# Hike_Buddy_Schematic.net
KiCad netlist of a schematic drawn in Altium Designer
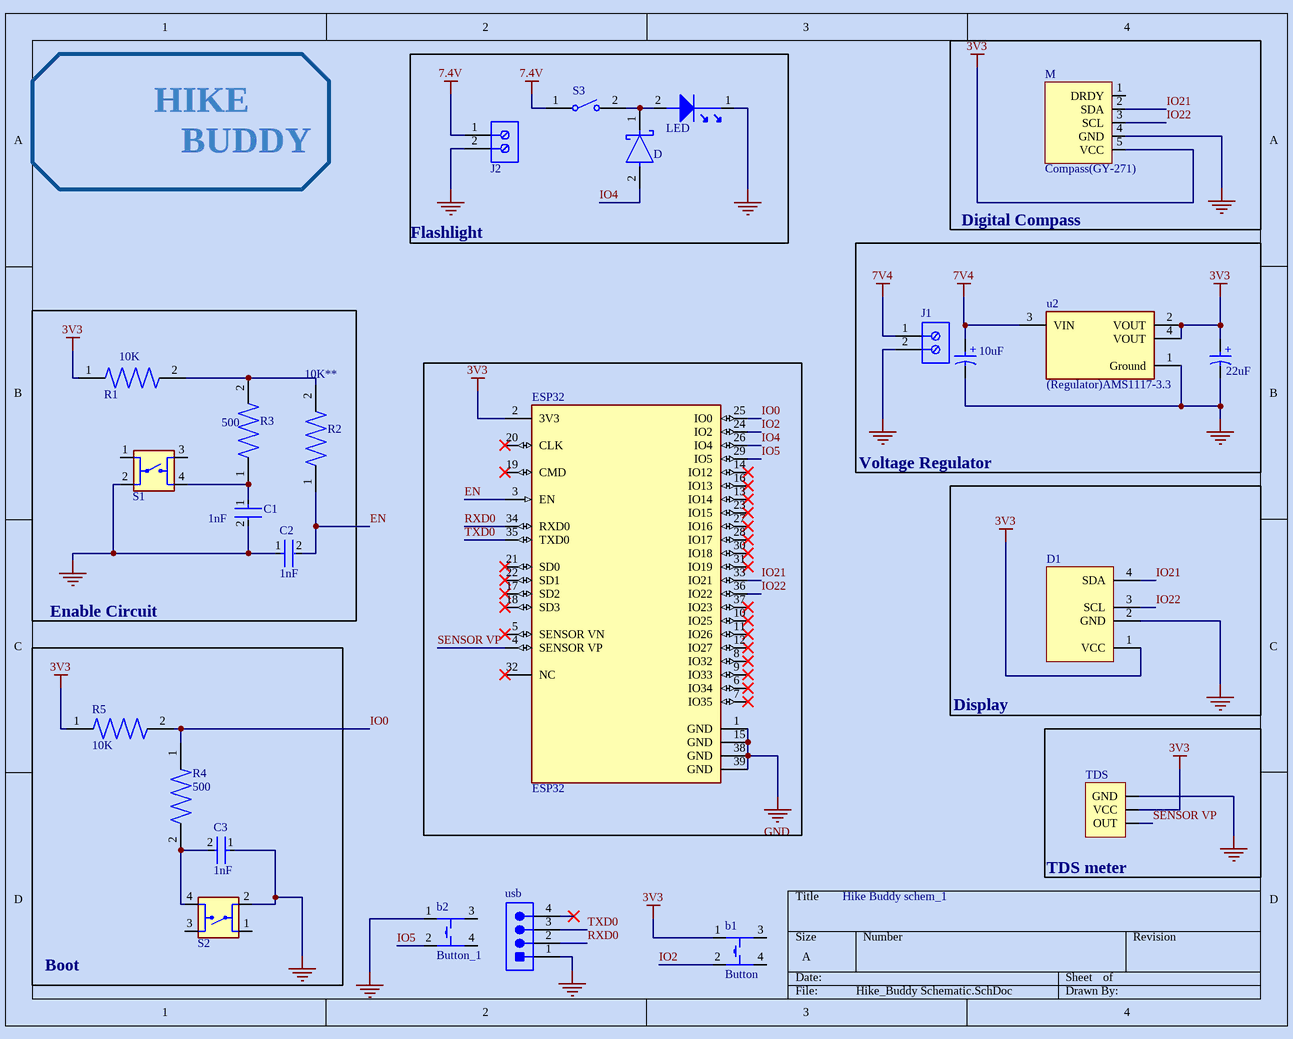
[diagram p0: Hike_Buddy Schematic.SchDoc]

(export (version "E")
  (design (tool "Eeschema 10.0.6"))
  (components
    (comp (ref "10uF")
      (value "860010372001")
      (footprint "WCAP-ATG8_D5H11")
      (description "860010372001 Cap Aluminum Lytic 10uF 16V 20% (5 X 11mm) Radial 2mm 44mA 2000h 85C")
      (fields (field (name "TOLERANCE") "20%"))
      (libsource (lib "Altium Content Vault") (part "Capacitor_Polarized"))
    )
    (comp (ref "22uF")
      (value "860020472004")
      (footprint "WCAP-ATG5_D5H11")
      (description "860020472004 WCAP-ATG5 Aluminum Electrolytic Capacitors")
      (fields (field (name "TOLERANCE") "20%"))
      (libsource (lib "Altium Content Vault") (part "Capacitor_Polarized"))
    )
    (comp (ref "b1")
      (value "Button")
      (footprint "Push Button")
      (libsource (lib "Hike_Buddy") (part "Button"))
    )
    (comp (ref "b2")
      (value "Button_1")
      (footprint "Push Button")
      (libsource (lib "Hike_Buddy") (part "Button_1"))
    )
    (comp (ref "C1")
      (value "1nF")
      (footprint "FP-VY2102M29Y5US6TV7-MFG")
      (fields (field (name "VOLTAGE") "300V") (field (name "TOLERANCE") "20%"))
      (libsource (lib "Altium Content Vault") (part "11868f565c42a9108669ba33697ecf6"))
    )
    (comp (ref "C2")
      (value "1nF")
      (footprint "FP-VY2102M29Y5US6TV7-MFG")
      (fields (field (name "VOLTAGE") "300V") (field (name "TOLERANCE") "20%"))
      (libsource (lib "Altium Content Vault") (part "11868f565c42a9108669ba33697ecf6"))
    )
    (comp (ref "C3")
      (value "1nF")
      (footprint "FP-VY2102M29Y5US6TV7-MFG")
      (fields (field (name "VOLTAGE") "300V") (field (name "TOLERANCE") "20%"))
      (libsource (lib "Altium Content Vault") (part "11868f565c42a9108669ba33697ecf6"))
    )
    (comp (ref "D")
      (value "1N5817")
      (footprint "FP-DO-41-MFG")
      (description "DIODE SCHOTTKY 20V 1A DO41")
      (libsource (lib "Altium Content Vault") (part "1d6ec82d83fb6aee721767c19dac4b9"))
    )
    (comp (ref "D1")
      (value "OLED Display")
      (footprint "Display")
      (description "0.96 inch 128X64 OLED Display Module Blue I2C IIC")
      (libsource (lib "Hike_Buddy") (part "Display"))
    )
    (comp (ref "ESP32")
      (value "ESP32")
      (footprint "ESP32")
      (description "ESP-WROOM-32")
      (libsource (lib "Hike_Buddy") (part "ESP32W"))
    )
    (comp (ref "J1")
      (value "282836-2")
      (footprint "TECO-282836-2_V")
      (description "Female Header, Pitch 5 mm, 1 x 2 Position, Height 10 mm, Tail Length 3.5 mm, Rohs, Bulk")
      (fields (field (name "VOLTAGE") "300V") (field (name "MANUFACTURER") "TE Connectivity"))
      (libsource (lib "Altium Content Vault") (part "CN-1P-F-TB2"))
    )
    (comp (ref "J2")
      (value "282836-2")
      (footprint "TECO-282836-2_V")
      (description "Female Header, Pitch 5 mm, 1 x 2 Position, Height 10 mm, Tail Length 3.5 mm, Rohs, Bulk")
      (fields (field (name "VOLTAGE") "300V") (field (name "MANUFACTURER") "TE Connectivity"))
      (libsource (lib "Altium Content Vault") (part "CN-1P-F-TB2"))
    )
    (comp (ref "L") (value "LED") (footprint "LED") (libsource (lib "Hike_Buddy") (part "LED")))
    (comp (ref "M")
      (value "Compass(GY-271)")
      (footprint "QMC")
      (description "GY-271 HMC5883L 3-Axis Compass Magnetometer Module")
      (libsource (lib "Hike_Buddy") (part "Magnetometer"))
    )
    (comp (ref "R1") (value "10K") (footprint "R1") (libsource (lib "Hike_Buddy") (part "R1")))
    (comp (ref "R2") (value "10K**") (footprint "R1") (libsource (lib "Hike_Buddy") (part "R2")))
    (comp (ref "R3") (value "500") (footprint "R1") (libsource (lib "Hike_Buddy") (part "R3")))
    (comp (ref "R4") (value "500") (footprint "R1") (libsource (lib "Hike_Buddy") (part "R4")))
    (comp (ref "R5") (value "10K") (footprint "R1") (libsource (lib "Hike_Buddy") (part "R5")))
    (comp (ref "S1") (value "Switch") (footprint "Switch") (libsource (lib "Hike_Buddy") (part "Switch")))
    (comp (ref "S2") (value "Switch2") (footprint "Switch") (libsource (lib "Hike_Buddy") (part "Switch2")))
    (comp (ref "S3")
      (value "FSMSM")
      (footprint "TECO-FSMSM-2_V")
      (description "FSMSM Push Button Switch, 50 mA, -35 to 85 degC, 2-Pin SMD, RoHS, Bulk")
      (fields (field (name "MANUFACTURER") "TE Connectivity"))
      (libsource (lib "Altium Content Vault") (part "SW-SPST-2_C"))
    )
    (comp (ref "TDS") (value "~") (footprint "tds") (libsource (lib "Hike_Buddy") (part "tds")))
    (comp (ref "u2")
      (value "(Regulator)AMS1117-3.3")
      (footprint "FP-AMS1117-IPC_C")
      (description "LDO Voltage Regulators 1A, 3.3V")
      (fields
        (field (name "MANUFACTURER PART NUMBER") "AMS1117-3.3")
        (field (name "OCTOPART") "https://octopart.com/ams1117-3.3-advanced+monolithic+systems-25899300")
      )
      (libsource (lib "Altium Content Vault") (part "8bdbb5f8e77002000e30dd2845d0354"))
    )
    (comp (ref "usb")
      (value "640456-4")
      (footprint "TECO-640456-4")
      (description "Male Header, Pitch 2.54 mm, 1 x 4 Position, Height 10.03 mm, Tail Length 3.56 mm, RoHS, Bulk")
      (fields (field (name "MANUFACTURER") "TE Connectivity"))
      (libsource (lib "Altium Content Vault") (part "CN-1P-M-R4"))
    )
  )
  (nets
    (net (code "2") (name "/EN") (class "Default")
      (node (ref "C2") (pin "2") (pinfunction "2_2") (pintype "passive"))
      (node (ref "ESP32") (pin "3") (pinfunction "EN_3") (pintype "input"))
      (node (ref "R2") (pin "1") (pinfunction "1_1") (pintype "passive"))
    )
    (net (code "3") (name "/IO0") (class "Default")
      (node (ref "ESP32") (pin "25") (pinfunction "IO0_25") (pintype "bidirectional"))
      (node (ref "R4") (pin "1") (pinfunction "1_1") (pintype "passive"))
      (node (ref "R5") (pin "2") (pinfunction "2_2") (pintype "passive"))
    )
    (net (code "4") (name "/IO2") (class "Default")
      (node (ref "ESP32") (pin "24") (pinfunction "IO2_24") (pintype "bidirectional"))
      (node (ref "b1") (pin "2") (pinfunction "2_2") (pintype "passive"))
    )
    (net (code "5") (name "/IO4") (class "Default")
      (node (ref "D") (pin "2") (pinfunction "A_2") (pintype "passive"))
      (node (ref "ESP32") (pin "26") (pinfunction "IO4_26") (pintype "bidirectional"))
    )
    (net (code "6") (name "/IO5") (class "Default")
      (node (ref "ESP32") (pin "29") (pinfunction "IO5_29") (pintype "bidirectional"))
      (node (ref "b2") (pin "2") (pinfunction "2_2") (pintype "passive"))
    )
    (net (code "7") (name "/IO21") (class "Default")
      (node (ref "D1") (pin "4") (pinfunction "SDA_4") (pintype "passive"))
      (node (ref "ESP32") (pin "33") (pinfunction "IO21_33") (pintype "bidirectional"))
      (node (ref "M") (pin "2") (pinfunction "SDA_2") (pintype "passive"))
    )
    (net (code "8") (name "/IO22") (class "Default")
      (node (ref "D1") (pin "3") (pinfunction "SCL_3") (pintype "passive"))
      (node (ref "ESP32") (pin "36") (pinfunction "IO22_36") (pintype "bidirectional"))
      (node (ref "M") (pin "3") (pinfunction "SCL_3") (pintype "passive"))
    )
    (net (code "9") (name "/RXD0") (class "Default")
      (node (ref "ESP32") (pin "34") (pinfunction "RXD0_34") (pintype "bidirectional"))
      (node (ref "usb") (pin "2") (pinfunction "2_2") (pintype "passive"))
    )
    (net (code "10") (name "/SENSOR VP") (class "Default")
      (node (ref "ESP32") (pin "4") (pinfunction "SENSOR_VP_4") (pintype "bidirectional"))
      (node (ref "TDS") (pin "3") (pinfunction "OUT_3") (pintype "passive"))
    )
    (net (code "11") (name "/TXD0") (class "Default")
      (node (ref "ESP32") (pin "35") (pinfunction "TXD0_35") (pintype "bidirectional"))
      (node (ref "usb") (pin "3") (pinfunction "3_3") (pintype "passive"))
    )
    (net (code "12") (name "3V3") (class "Default")
      (node (ref "22uF") (pin "1") (pinfunction "P_1") (pintype "passive"))
      (node (ref "D1") (pin "1") (pinfunction "VCC_1") (pintype "power_in"))
      (node (ref "ESP32") (pin "2") (pinfunction "3V3_2") (pintype "power_in"))
      (node (ref "M") (pin "5") (pinfunction "VCC_5") (pintype "passive"))
      (node (ref "R1") (pin "1") (pinfunction "1_1") (pintype "passive"))
      (node (ref "R5") (pin "1") (pinfunction "1_1") (pintype "passive"))
      (node (ref "TDS") (pin "2") (pinfunction "VCC_2") (pintype "passive"))
      (node (ref "b1") (pin "1") (pinfunction "1_1") (pintype "passive"))
      (node (ref "u2") (pin "2") (pinfunction "VOUT_2") (pintype "passive"))
      (node (ref "u2") (pin "4") (pinfunction "VOUT_4") (pintype "passive"))
    )
    (net (code "13") (name "7.4V") (class "Default")
      (node (ref "J2") (pin "1") (pinfunction "1_1") (pintype "passive"))
      (node (ref "S3") (pin "1") (pinfunction "1_1") (pintype "passive"))
    )
    (net (code "14") (name "7V4") (class "Default")
      (node (ref "10uF") (pin "1") (pinfunction "P_1") (pintype "passive"))
      (node (ref "J1") (pin "1") (pinfunction "1_1") (pintype "passive"))
      (node (ref "u2") (pin "3") (pinfunction "VIN_3") (pintype "power_in"))
    )
    (net (code "15") (name "GND") (class "Default")
      (node (ref "10uF") (pin "2") (pinfunction "N_2") (pintype "passive"))
      (node (ref "22uF") (pin "2") (pinfunction "N_2") (pintype "passive"))
      (node (ref "C1") (pin "2") (pinfunction "2_2") (pintype "passive"))
      (node (ref "C2") (pin "1") (pinfunction "1_1") (pintype "passive"))
      (node (ref "C3") (pin "1") (pinfunction "1_1") (pintype "passive"))
      (node (ref "D1") (pin "2") (pinfunction "GND_2") (pintype "power_in"))
      (node (ref "ESP32") (pin "1") (pinfunction "GND_1") (pintype "power_in"))
      (node (ref "ESP32") (pin "15") (pinfunction "GND_15") (pintype "power_in"))
      (node (ref "ESP32") (pin "38") (pinfunction "GND_38") (pintype "power_in"))
      (node (ref "ESP32") (pin "39") (pinfunction "GND_39") (pintype "power_in"))
      (node (ref "J1") (pin "2") (pinfunction "2_2") (pintype "passive"))
      (node (ref "J2") (pin "2") (pinfunction "2_2") (pintype "passive"))
      (node (ref "L") (pin "1") (pinfunction "1_1") (pintype "passive"))
      (node (ref "M") (pin "4") (pinfunction "GND_4") (pintype "passive"))
      (node (ref "S1") (pin "2") (pinfunction "2_2") (pintype "passive"))
      (node (ref "S2") (pin "2") (pinfunction "2_2") (pintype "passive"))
      (node (ref "TDS") (pin "1") (pinfunction "GND_1") (pintype "passive"))
      (node (ref "b2") (pin "1") (pinfunction "1_1") (pintype "passive"))
      (node (ref "u2") (pin "1") (pinfunction "Ground_1") (pintype "power_in"))
      (node (ref "usb") (pin "1") (pinfunction "1_1") (pintype "passive"))
    )
    (net (code "16") (name "Net-(C1-Pad1)") (class "Default")
      (node (ref "C1") (pin "1") (pinfunction "1_1") (pintype "passive"))
      (node (ref "R3") (pin "1") (pinfunction "1_1") (pintype "passive"))
      (node (ref "S1") (pin "4") (pinfunction "4_4") (pintype "passive"))
    )
    (net (code "17") (name "Net-(C3-Pad2)") (class "Default")
      (node (ref "C3") (pin "2") (pinfunction "2_2") (pintype "passive"))
      (node (ref "R4") (pin "2") (pinfunction "2_2") (pintype "passive"))
      (node (ref "S2") (pin "4") (pinfunction "4_4") (pintype "passive"))
    )
    (net (code "18") (name "Net-(D-C)") (class "Default")
      (node (ref "D") (pin "1") (pinfunction "C_1") (pintype "passive"))
      (node (ref "L") (pin "2") (pinfunction "2_2") (pintype "passive"))
      (node (ref "S3") (pin "2") (pinfunction "2_2") (pintype "passive"))
    )
    (net (code "19") (name "Net-(R1-Pad2)") (class "Default")
      (node (ref "R1") (pin "2") (pinfunction "2_2") (pintype "passive"))
      (node (ref "R2") (pin "2") (pinfunction "2_2") (pintype "passive"))
      (node (ref "R3") (pin "2") (pinfunction "2_2") (pintype "passive"))
    )
    (net (code "20") (name "unconnected-(ESP32-CLK-Pad20)") (class "Default")
      (node (ref "ESP32") (pin "20") (pinfunction "CLK_20") (pintype "bidirectional+no_connect"))
    )
    (net (code "21") (name "unconnected-(ESP32-CMD-Pad19)") (class "Default")
      (node (ref "ESP32") (pin "19") (pinfunction "CMD_19") (pintype "bidirectional+no_connect"))
    )
    (net (code "22") (name "unconnected-(ESP32-IO12-Pad14)") (class "Default")
      (node (ref "ESP32") (pin "14") (pinfunction "IO12_14") (pintype "bidirectional+no_connect"))
    )
    (net (code "23") (name "unconnected-(ESP32-IO13-Pad16)") (class "Default")
      (node (ref "ESP32") (pin "16") (pinfunction "IO13_16") (pintype "bidirectional+no_connect"))
    )
    (net (code "24") (name "unconnected-(ESP32-IO14-Pad13)") (class "Default")
      (node (ref "ESP32") (pin "13") (pinfunction "IO14_13") (pintype "bidirectional+no_connect"))
    )
    (net (code "25") (name "unconnected-(ESP32-IO15-Pad23)") (class "Default")
      (node (ref "ESP32") (pin "23") (pinfunction "IO15_23") (pintype "bidirectional+no_connect"))
    )
    (net (code "26") (name "unconnected-(ESP32-IO16-Pad27)") (class "Default")
      (node (ref "ESP32") (pin "27") (pinfunction "IO16_27") (pintype "bidirectional+no_connect"))
    )
    (net (code "27") (name "unconnected-(ESP32-IO17-Pad28)") (class "Default")
      (node (ref "ESP32") (pin "28") (pinfunction "IO17_28") (pintype "bidirectional+no_connect"))
    )
    (net (code "28") (name "unconnected-(ESP32-IO18-Pad30)") (class "Default")
      (node (ref "ESP32") (pin "30") (pinfunction "IO18_30") (pintype "bidirectional+no_connect"))
    )
    (net (code "29") (name "unconnected-(ESP32-IO19-Pad31)") (class "Default")
      (node (ref "ESP32") (pin "31") (pinfunction "IO19_31") (pintype "bidirectional+no_connect"))
    )
    (net (code "30") (name "unconnected-(ESP32-IO23-Pad37)") (class "Default")
      (node (ref "ESP32") (pin "37") (pinfunction "IO23_37") (pintype "bidirectional+no_connect"))
    )
    (net (code "31") (name "unconnected-(ESP32-IO25-Pad10)") (class "Default")
      (node (ref "ESP32") (pin "10") (pinfunction "IO25_10") (pintype "bidirectional+no_connect"))
    )
    (net (code "32") (name "unconnected-(ESP32-IO26-Pad11)") (class "Default")
      (node (ref "ESP32") (pin "11") (pinfunction "IO26_11") (pintype "bidirectional+no_connect"))
    )
    (net (code "33") (name "unconnected-(ESP32-IO27-Pad12)") (class "Default")
      (node (ref "ESP32") (pin "12") (pinfunction "IO27_12") (pintype "bidirectional+no_connect"))
    )
    (net (code "34") (name "unconnected-(ESP32-IO32-Pad8)") (class "Default")
      (node (ref "ESP32") (pin "8") (pinfunction "IO32_8") (pintype "bidirectional+no_connect"))
    )
    (net (code "35") (name "unconnected-(ESP32-IO33-Pad9)") (class "Default")
      (node (ref "ESP32") (pin "9") (pinfunction "IO33_9") (pintype "bidirectional+no_connect"))
    )
    (net (code "36") (name "unconnected-(ESP32-IO34-Pad6)") (class "Default")
      (node (ref "ESP32") (pin "6") (pinfunction "IO34_6") (pintype "bidirectional+no_connect"))
    )
    (net (code "37") (name "unconnected-(ESP32-IO35-Pad7)") (class "Default")
      (node (ref "ESP32") (pin "7") (pinfunction "IO35_7") (pintype "bidirectional+no_connect"))
    )
    (net (code "38") (name "unconnected-(ESP32-NC-Pad32)") (class "Default")
      (node (ref "ESP32") (pin "32") (pinfunction "NC_32") (pintype "passive+no_connect"))
    )
    (net (code "39") (name "unconnected-(ESP32-SD0-Pad21)") (class "Default")
      (node (ref "ESP32") (pin "21") (pinfunction "SD0_21") (pintype "bidirectional+no_connect"))
    )
    (net (code "40") (name "unconnected-(ESP32-SD1-Pad22)") (class "Default")
      (node (ref "ESP32") (pin "22") (pinfunction "SD1_22") (pintype "bidirectional+no_connect"))
    )
    (net (code "41") (name "unconnected-(ESP32-SD2-Pad17)") (class "Default")
      (node (ref "ESP32") (pin "17") (pinfunction "SD2_17") (pintype "bidirectional+no_connect"))
    )
    (net (code "42") (name "unconnected-(ESP32-SD3-Pad18)") (class "Default")
      (node (ref "ESP32") (pin "18") (pinfunction "SD3_18") (pintype "bidirectional+no_connect"))
    )
    (net (code "43") (name "unconnected-(ESP32-SENSOR_VN-Pad5)") (class "Default")
      (node (ref "ESP32") (pin "5") (pinfunction "SENSOR_VN_5") (pintype "bidirectional+no_connect"))
    )
    (net (code "44") (name "unconnected-(M-DRDY-Pad1)") (class "Default")
      (node (ref "M") (pin "1") (pinfunction "DRDY_1") (pintype "passive"))
    )
    (net (code "45") (name "unconnected-(S1-Pad1)") (class "Default")
      (node (ref "S1") (pin "1") (pinfunction "1_1") (pintype "passive"))
    )
    (net (code "46") (name "unconnected-(S1-Pad3)") (class "Default")
      (node (ref "S1") (pin "3") (pinfunction "3_3") (pintype "passive"))
    )
    (net (code "47") (name "unconnected-(S2-Pad1)") (class "Default")
      (node (ref "S2") (pin "1") (pinfunction "1_1") (pintype "passive"))
    )
    (net (code "48") (name "unconnected-(S2-Pad3)") (class "Default")
      (node (ref "S2") (pin "3") (pinfunction "3_3") (pintype "passive"))
    )
    (net (code "49") (name "unconnected-(b1-Pad3)") (class "Default")
      (node (ref "b1") (pin "3") (pinfunction "3_3") (pintype "passive"))
    )
    (net (code "50") (name "unconnected-(b1-Pad4)") (class "Default")
      (node (ref "b1") (pin "4") (pinfunction "4_4") (pintype "passive"))
    )
    (net (code "51") (name "unconnected-(b2-Pad3)") (class "Default")
      (node (ref "b2") (pin "3") (pinfunction "3_3") (pintype "passive"))
    )
    (net (code "52") (name "unconnected-(b2-Pad4)") (class "Default")
      (node (ref "b2") (pin "4") (pinfunction "4_4") (pintype "passive"))
    )
    (net (code "53") (name "unconnected-(usb-Pad4)") (class "Default")
      (node (ref "usb") (pin "4") (pinfunction "4_4") (pintype "passive+no_connect"))
    )
  )
)
